# RGB-Controller.net
KiCad netlist of a schematic drawn in EasyEDA
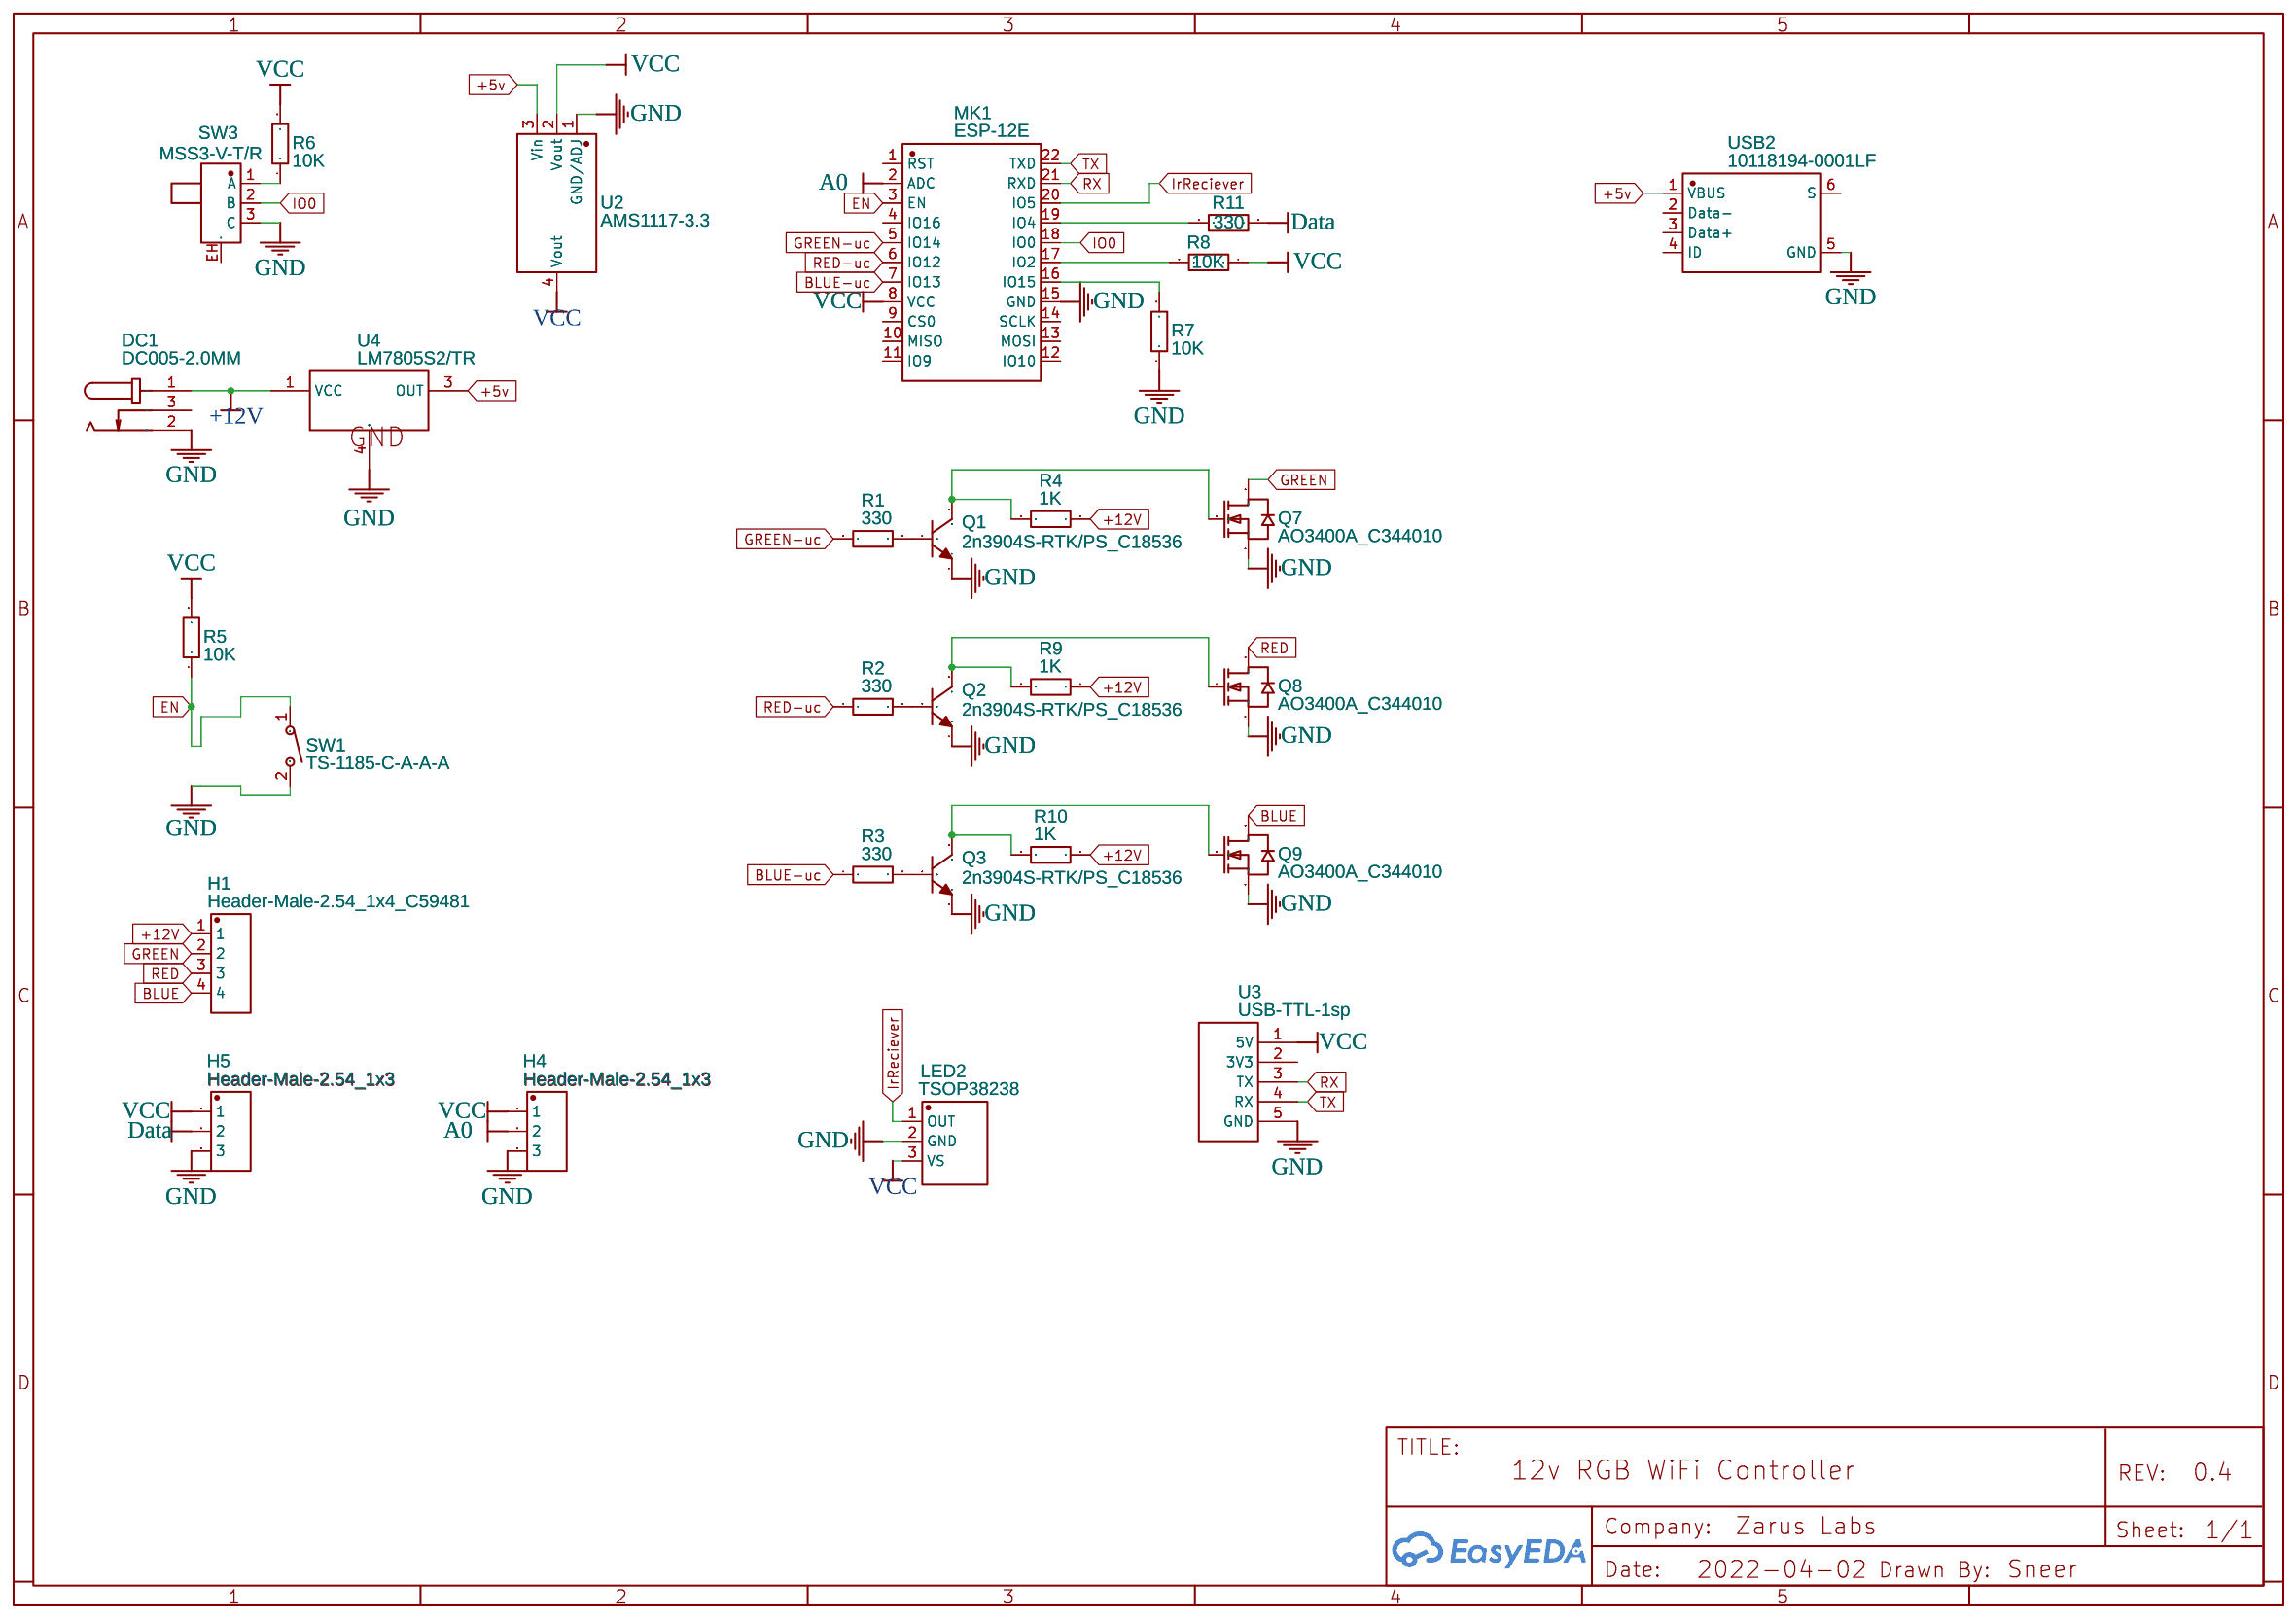
[diagram p0: schematic sheet]

(export (version "E")
  (design (tool "Eeschema 10.0.6"))
  (components
    (comp (ref "DC1")
      (value "DC005-2.0MM")
      (fields (field (name "BOM_Supplier Part") "C111567"))
      (libsource (lib "") (part "DC005-2.0MM"))
    )
    (comp (ref "H1")
      (value "Header-Male-2.54_1x4_C59481")
      (fields
        (field (name "BOM_Manufacturer Part") "Headers  Pins 1*4P")
        (field (name "BOM_Supplier Part") "C59481")
      )
      (libsource (lib "") (part "Header-Male-2.54_1x4_C59481"))
    )
    (comp (ref "H4") (value "Header-Male-2.54_1x3") (libsource (lib "") (part "Header-Male-2.54_1x3")))
    (comp (ref "H5") (value "Header-Male-2.54_1x3") (libsource (lib "") (part "Header-Male-2.54_1x3")))
    (comp (ref "LED2")
      (value "TSOP38238")
      (fields (field (name "BOM_Supplier Part") "C141632"))
      (libsource (lib "") (part "TSOP38238"))
    )
    (comp (ref "MK1")
      (value "ESP-12E")
      (fields (field (name "BOM_Supplier Part") "C89297"))
      (libsource (lib "") (part "ESP-12E"))
    )
    (comp (ref "Q1")
      (value "2n3904S-RTK/PS_C18536")
      (fields
        (field (name "BOM_Manufacturer Part") "2n3904S-RTK/PS")
        (field (name "BOM_Supplier Part") "C18536")
      )
      (libsource (lib "") (part "2n3904S-RTK/PS_C18536"))
    )
    (comp (ref "Q2")
      (value "2n3904S-RTK/PS_C18536")
      (fields
        (field (name "BOM_Manufacturer Part") "2n3904S-RTK/PS")
        (field (name "BOM_Supplier Part") "C18536")
      )
      (libsource (lib "") (part "2n3904S-RTK/PS_C18536"))
    )
    (comp (ref "Q3")
      (value "2n3904S-RTK/PS_C18536")
      (fields
        (field (name "BOM_Manufacturer Part") "2n3904S-RTK/PS")
        (field (name "BOM_Supplier Part") "C18536")
      )
      (libsource (lib "") (part "2n3904S-RTK/PS_C18536"))
    )
    (comp (ref "Q7")
      (value "AO3400A_C344010")
      (fields (field (name "BOM_Manufacturer Part") "AO3400A") (field (name "BOM_Supplier Part") "C344010"))
      (libsource (lib "") (part "AO3400A_C344010"))
    )
    (comp (ref "Q8")
      (value "AO3400A_C344010")
      (fields (field (name "BOM_Manufacturer Part") "AO3400A") (field (name "BOM_Supplier Part") "C344010"))
      (libsource (lib "") (part "AO3400A_C344010"))
    )
    (comp (ref "Q9")
      (value "AO3400A_C344010")
      (fields (field (name "BOM_Manufacturer Part") "AO3400A") (field (name "BOM_Supplier Part") "C344010"))
      (libsource (lib "") (part "AO3400A_C344010"))
    )
    (comp (ref "R1")
      (value "330")
      (fields
        (field (name "BOM_Manufacturer Part") "0805W8J0331T5E")
        (field (name "BOM_Supplier Part") "C25306")
      )
      (libsource (lib "") (part "0805W8J0331T5E"))
    )
    (comp (ref "R2")
      (value "330")
      (fields
        (field (name "BOM_Manufacturer Part") "0805W8J0331T5E")
        (field (name "BOM_Supplier Part") "C25306")
      )
      (libsource (lib "") (part "0805W8J0331T5E"))
    )
    (comp (ref "R3")
      (value "330")
      (fields
        (field (name "BOM_Manufacturer Part") "0805W8J0331T5E")
        (field (name "BOM_Supplier Part") "C25306")
      )
      (libsource (lib "") (part "0805W8J0331T5E"))
    )
    (comp (ref "R4")
      (value "1K")
      (fields
        (field (name "BOM_Manufacturer Part") "1210W3J0102T5E")
        (field (name "BOM_Supplier Part") "C25681")
      )
      (libsource (lib "") (part "1210W3J0102T5E"))
    )
    (comp (ref "R5")
      (value "10K")
      (fields
        (field (name "BOM_Manufacturer Part") "1206W4F1002T5E")
        (field (name "BOM_Supplier Part") "C17902")
      )
      (libsource (lib "") (part "1206W4F1002T5E"))
    )
    (comp (ref "R6")
      (value "10K")
      (fields
        (field (name "BOM_Manufacturer Part") "1206W4F1002T5E")
        (field (name "BOM_Supplier Part") "C17902")
      )
      (libsource (lib "") (part "1206W4F1002T5E"))
    )
    (comp (ref "R7")
      (value "10K")
      (fields
        (field (name "BOM_Manufacturer Part") "1206W4F1002T5E")
        (field (name "BOM_Supplier Part") "C17902")
      )
      (libsource (lib "") (part "1206W4F1002T5E"))
    )
    (comp (ref "R8")
      (value "10K")
      (fields
        (field (name "BOM_Manufacturer Part") "1206W4F1002T5E")
        (field (name "BOM_Supplier Part") "C17902")
      )
      (libsource (lib "") (part "1206W4F1002T5E_1"))
    )
    (comp (ref "R9")
      (value "1K")
      (fields
        (field (name "BOM_Manufacturer Part") "1210W3J0102T5E")
        (field (name "BOM_Supplier Part") "C25681")
      )
      (libsource (lib "") (part "1210W3J0102T5E"))
    )
    (comp (ref "R10")
      (value "1K")
      (fields
        (field (name "BOM_Manufacturer Part") "1210W3J0102T5E")
        (field (name "BOM_Supplier Part") "C25681")
      )
      (libsource (lib "") (part "1210W3J0102T5E"))
    )
    (comp (ref "R11")
      (value "330")
      (fields
        (field (name "BOM_Manufacturer Part") "0805W8J0331T5E")
        (field (name "BOM_Supplier Part") "C25306")
      )
      (libsource (lib "") (part "0805W8J0331T5E"))
    )
    (comp (ref "SW1")
      (value "TS-1185-C-A-A-A")
      (fields (field (name "BOM_Supplier Part") "C561518"))
      (libsource (lib "") (part "TS-1185-C-A-A-A"))
    )
    (comp (ref "SW3")
      (value "MSS3-V-T/R")
      (fields (field (name "BOM_Supplier Part") "C495932"))
      (libsource (lib "") (part "MSS3-V-T/R"))
    )
    (comp (ref "U2")
      (value "AMS1117-3.3")
      (fields (field (name "BOM_Supplier Part") "C6186"))
      (libsource (lib "") (part "AMS1117-3.3"))
    )
    (comp (ref "U3") (value "USB-TTL-1sp") (libsource (lib "") (part "USB-TTL-1sp")))
    (comp (ref "U4")
      (value "LM7805S2/TR")
      (fields (field (name "BOM_Supplier Part") "C2902505"))
      (libsource (lib "") (part "LM7805S2/TR"))
    )
    (comp (ref "USB2")
      (value "10118194-0001LF")
      (fields (field (name "BOM_Supplier Part") "C132563"))
      (libsource (lib "") (part "10118194-0001LF"))
    )
  )
  (nets
    (net (code "1") (name "+5v") (class "Default")
      (node (ref "U2") (pin "3") (pinfunction "Vin_3") (pintype "unspecified"))
      (node (ref "U4") (pin "3") (pinfunction "OUT_3") (pintype "passive"))
      (node (ref "USB2") (pin "1") (pinfunction "VBUS_1") (pintype "unspecified"))
    )
    (net (code "2") (name "+12V") (class "Default")
      (node (ref "DC1") (pin "1") (pinfunction "1_1") (pintype "unspecified"))
      (node (ref "H1") (pin "1") (pinfunction "1_1") (pintype "unspecified"))
      (node (ref "R10") (pin "1") (pinfunction "1_1") (pintype "input"))
      (node (ref "R4") (pin "1") (pinfunction "1_1") (pintype "input"))
      (node (ref "R9") (pin "1") (pinfunction "1_1") (pintype "input"))
      (node (ref "U4") (pin "1") (pinfunction "VCC_1") (pintype "passive"))
    )
    (net (code "3") (name "A0") (class "Default")
      (node (ref "H4") (pin "2") (pinfunction "2_2") (pintype "unspecified"))
      (node (ref "MK1") (pin "2") (pinfunction "ADC_2") (pintype "unspecified"))
    )
    (net (code "4") (name "BLUE") (class "Default")
      (node (ref "H1") (pin "4") (pinfunction "4_4") (pintype "unspecified"))
      (node (ref "Q9") (pin "3") (pinfunction "D_3") (pintype "unspecified"))
    )
    (net (code "5") (name "BLUE-uc") (class "Default")
      (node (ref "MK1") (pin "7") (pinfunction "IO13_7") (pintype "unspecified"))
      (node (ref "R3") (pin "1") (pinfunction "1_1") (pintype "input"))
    )
    (net (code "6") (name "Data") (class "Default")
      (node (ref "H5") (pin "2") (pinfunction "2_2") (pintype "unspecified"))
      (node (ref "R11") (pin "2") (pinfunction "2_2") (pintype "input"))
    )
    (net (code "7") (name "EN") (class "Default")
      (node (ref "MK1") (pin "3") (pinfunction "EN_3") (pintype "unspecified"))
      (node (ref "R5") (pin "1") (pinfunction "1_1") (pintype "input"))
      (node (ref "SW1") (pin "1") (pinfunction "1_1") (pintype "unspecified"))
    )
    (net (code "8") (name "GND") (class "Default")
      (node (ref "DC1") (pin "2") (pinfunction "2_2") (pintype "unspecified"))
      (node (ref "H4") (pin "3") (pinfunction "3_3") (pintype "unspecified"))
      (node (ref "H5") (pin "3") (pinfunction "3_3") (pintype "unspecified"))
      (node (ref "LED2") (pin "2") (pinfunction "GND_2") (pintype "unspecified"))
      (node (ref "MK1") (pin "15") (pinfunction "GND_15") (pintype "unspecified"))
      (node (ref "Q1") (pin "1") (pinfunction "E_1") (pintype "input"))
      (node (ref "Q2") (pin "1") (pinfunction "E_1") (pintype "input"))
      (node (ref "Q3") (pin "1") (pinfunction "E_1") (pintype "input"))
      (node (ref "Q7") (pin "2") (pinfunction "S_2") (pintype "unspecified"))
      (node (ref "Q8") (pin "2") (pinfunction "S_2") (pintype "unspecified"))
      (node (ref "Q9") (pin "2") (pinfunction "S_2") (pintype "unspecified"))
      (node (ref "R7") (pin "1") (pinfunction "1_1") (pintype "input"))
      (node (ref "SW1") (pin "2") (pinfunction "2_2") (pintype "unspecified"))
      (node (ref "SW3") (pin "3") (pinfunction "C_3") (pintype "unspecified"))
      (node (ref "U2") (pin "1") (pinfunction "GND/ADJ_1") (pintype "unspecified"))
      (node (ref "U3") (pin "5") (pinfunction "GND_5") (pintype "passive"))
      (node (ref "U4") (pin "4") (pinfunction "GND_4") (pintype "passive"))
      (node (ref "USB2") (pin "5") (pinfunction "GND_5") (pintype "unspecified"))
    )
    (net (code "9") (name "GREEN") (class "Default")
      (node (ref "H1") (pin "2") (pinfunction "2_2") (pintype "unspecified"))
      (node (ref "Q7") (pin "3") (pinfunction "D_3") (pintype "unspecified"))
    )
    (net (code "10") (name "GREEN-uc") (class "Default")
      (node (ref "MK1") (pin "5") (pinfunction "IO14_5") (pintype "unspecified"))
      (node (ref "R1") (pin "1") (pinfunction "1_1") (pintype "input"))
    )
    (net (code "11") (name "IO0") (class "Default")
      (node (ref "MK1") (pin "18") (pinfunction "IO0_18") (pintype "unspecified"))
      (node (ref "SW3") (pin "2") (pinfunction "B_2") (pintype "unspecified"))
    )
    (net (code "12") (name "IrReciever") (class "Default")
      (node (ref "LED2") (pin "1") (pinfunction "OUT_1") (pintype "unspecified"))
      (node (ref "MK1") (pin "20") (pinfunction "IO5_20") (pintype "unspecified"))
    )
    (net (code "13") (name "Net-(MK1-IO2)") (class "Default")
      (node (ref "MK1") (pin "17") (pinfunction "IO2_17") (pintype "unspecified"))
      (node (ref "R8") (pin "2") (pinfunction "2_2") (pintype "input"))
    )
    (net (code "14") (name "Net-(MK1-IO4)") (class "Default")
      (node (ref "MK1") (pin "19") (pinfunction "IO4_19") (pintype "unspecified"))
      (node (ref "R11") (pin "1") (pinfunction "1_1") (pintype "input"))
    )
    (net (code "15") (name "Net-(MK1-IO15)") (class "Default")
      (node (ref "MK1") (pin "16") (pinfunction "IO15_16") (pintype "unspecified"))
      (node (ref "R7") (pin "2") (pinfunction "2_2") (pintype "input"))
    )
    (net (code "16") (name "Net-(Q1-B)") (class "Default")
      (node (ref "Q1") (pin "2") (pinfunction "B_2") (pintype "input"))
      (node (ref "R1") (pin "2") (pinfunction "2_2") (pintype "input"))
    )
    (net (code "17") (name "Net-(Q1-C)") (class "Default")
      (node (ref "Q1") (pin "3") (pinfunction "C_3") (pintype "input"))
      (node (ref "Q7") (pin "1") (pinfunction "G_1") (pintype "unspecified"))
      (node (ref "R4") (pin "2") (pinfunction "2_2") (pintype "input"))
    )
    (net (code "18") (name "Net-(Q2-B)") (class "Default")
      (node (ref "Q2") (pin "2") (pinfunction "B_2") (pintype "input"))
      (node (ref "R2") (pin "2") (pinfunction "2_2") (pintype "input"))
    )
    (net (code "19") (name "Net-(Q2-C)") (class "Default")
      (node (ref "Q2") (pin "3") (pinfunction "C_3") (pintype "input"))
      (node (ref "Q8") (pin "1") (pinfunction "G_1") (pintype "unspecified"))
      (node (ref "R9") (pin "2") (pinfunction "2_2") (pintype "input"))
    )
    (net (code "20") (name "Net-(Q3-B)") (class "Default")
      (node (ref "Q3") (pin "2") (pinfunction "B_2") (pintype "input"))
      (node (ref "R3") (pin "2") (pinfunction "2_2") (pintype "input"))
    )
    (net (code "21") (name "Net-(Q3-C)") (class "Default")
      (node (ref "Q3") (pin "3") (pinfunction "C_3") (pintype "input"))
      (node (ref "Q9") (pin "1") (pinfunction "G_1") (pintype "unspecified"))
      (node (ref "R10") (pin "2") (pinfunction "2_2") (pintype "input"))
    )
    (net (code "22") (name "Net-(SW3-A)") (class "Default")
      (node (ref "R6") (pin "1") (pinfunction "1_1") (pintype "input"))
      (node (ref "SW3") (pin "1") (pinfunction "A_1") (pintype "unspecified"))
    )
    (net (code "23") (name "RED") (class "Default")
      (node (ref "H1") (pin "3") (pinfunction "3_3") (pintype "unspecified"))
      (node (ref "Q8") (pin "3") (pinfunction "D_3") (pintype "unspecified"))
    )
    (net (code "24") (name "RED-uc") (class "Default")
      (node (ref "MK1") (pin "6") (pinfunction "IO12_6") (pintype "unspecified"))
      (node (ref "R2") (pin "1") (pinfunction "1_1") (pintype "input"))
    )
    (net (code "25") (name "RX") (class "Default")
      (node (ref "MK1") (pin "21") (pinfunction "RXD_21") (pintype "unspecified"))
      (node (ref "U3") (pin "3") (pinfunction "TX_3") (pintype "output"))
    )
    (net (code "26") (name "TX") (class "Default")
      (node (ref "MK1") (pin "22") (pinfunction "TXD_22") (pintype "unspecified"))
      (node (ref "U3") (pin "4") (pinfunction "RX_4") (pintype "output"))
    )
    (net (code "27") (name "VCC") (class "Default")
      (node (ref "H4") (pin "1") (pinfunction "1_1") (pintype "unspecified"))
      (node (ref "H5") (pin "1") (pinfunction "1_1") (pintype "unspecified"))
      (node (ref "LED2") (pin "3") (pinfunction "VS_3") (pintype "unspecified"))
      (node (ref "MK1") (pin "8") (pinfunction "VCC_8") (pintype "unspecified"))
      (node (ref "R5") (pin "2") (pinfunction "2_2") (pintype "input"))
      (node (ref "R6") (pin "2") (pinfunction "2_2") (pintype "input"))
      (node (ref "R8") (pin "1") (pinfunction "1_1") (pintype "input"))
      (node (ref "U2") (pin "2") (pinfunction "Vout_2") (pintype "unspecified"))
      (node (ref "U2") (pin "4") (pinfunction "Vout_4") (pintype "unspecified"))
      (node (ref "U3") (pin "1") (pinfunction "5V_1") (pintype "unspecified"))
    )
    (net (code "28") (name "unconnected-(DC1-Pad3)") (class "Default")
      (node (ref "DC1") (pin "3") (pinfunction "3_3") (pintype "unspecified"))
    )
    (net (code "29") (name "unconnected-(MK1-CS0-Pad9)") (class "Default")
      (node (ref "MK1") (pin "9") (pinfunction "CS0_9") (pintype "unspecified"))
    )
    (net (code "30") (name "unconnected-(MK1-IO9-Pad11)") (class "Default")
      (node (ref "MK1") (pin "11") (pinfunction "IO9_11") (pintype "unspecified"))
    )
    (net (code "31") (name "unconnected-(MK1-IO10-Pad12)") (class "Default")
      (node (ref "MK1") (pin "12") (pinfunction "IO10_12") (pintype "unspecified"))
    )
    (net (code "32") (name "unconnected-(MK1-IO16-Pad4)") (class "Default")
      (node (ref "MK1") (pin "4") (pinfunction "IO16_4") (pintype "unspecified"))
    )
    (net (code "33") (name "unconnected-(MK1-MISO-Pad10)") (class "Default")
      (node (ref "MK1") (pin "10") (pinfunction "MISO_10") (pintype "unspecified"))
    )
    (net (code "34") (name "unconnected-(MK1-MOSI-Pad13)") (class "Default")
      (node (ref "MK1") (pin "13") (pinfunction "MOSI_13") (pintype "unspecified"))
    )
    (net (code "35") (name "unconnected-(MK1-RST-Pad1)") (class "Default")
      (node (ref "MK1") (pin "1") (pinfunction "RST_1") (pintype "unspecified"))
    )
    (net (code "36") (name "unconnected-(MK1-SCLK-Pad14)") (class "Default")
      (node (ref "MK1") (pin "14") (pinfunction "SCLK_14") (pintype "unspecified"))
    )
    (net (code "37") (name "unconnected-(SW3-PadEH)") (class "Default")
      (node (ref "SW3") (pin "EH") (pinfunction "EH_EH") (pintype "unspecified"))
    )
    (net (code "38") (name "unconnected-(U3-3V3-Pad2)") (class "Default")
      (node (ref "U3") (pin "2") (pinfunction "3V3_2") (pintype "passive"))
    )
    (net (code "39") (name "unconnected-(USB2-Data+-Pad3)") (class "Default")
      (node (ref "USB2") (pin "3") (pinfunction "Data+_3") (pintype "unspecified"))
    )
    (net (code "40") (name "unconnected-(USB2-Data--Pad2)") (class "Default")
      (node (ref "USB2") (pin "2") (pinfunction "Data-_2") (pintype "unspecified"))
    )
    (net (code "41") (name "unconnected-(USB2-ID-Pad4)") (class "Default")
      (node (ref "USB2") (pin "4") (pinfunction "ID_4") (pintype "unspecified"))
    )
    (net (code "42") (name "unconnected-(USB2-S-Pad6)") (class "Default")
      (node (ref "USB2") (pin "6") (pinfunction "S_6") (pintype "unspecified"))
    )
  )
)
